# Sensores.net
KiCad netlist of a schematic drawn in Altium Designer
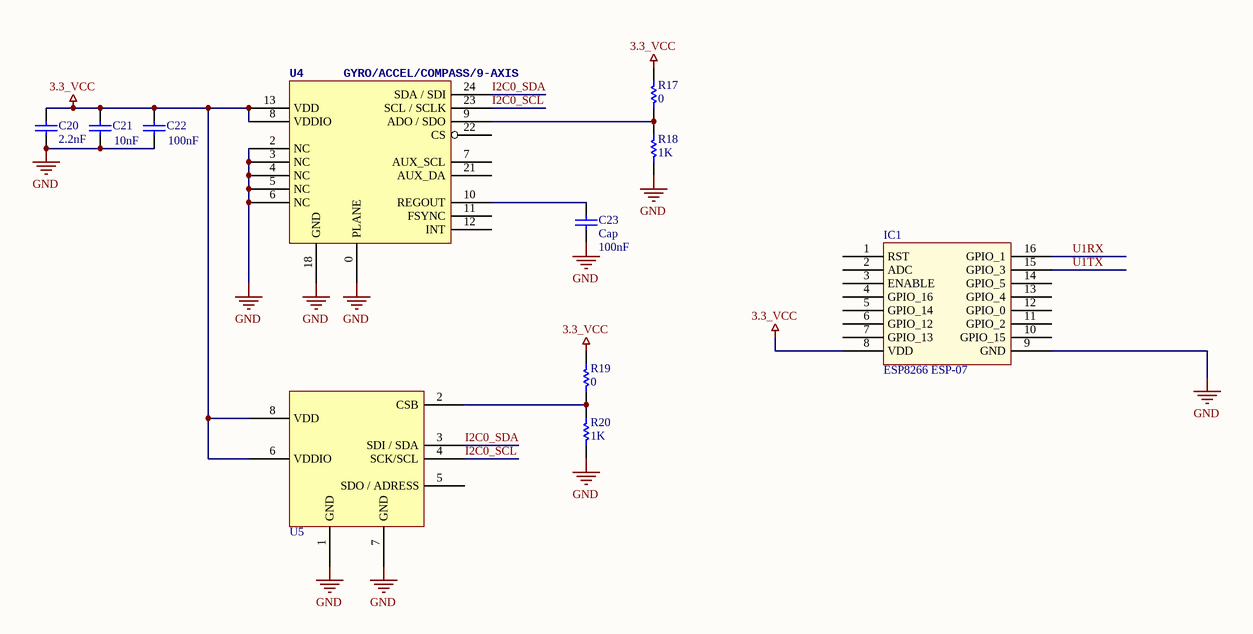
[diagram p0: Sensores.SchDoc]

(export (version "E")
  (design (tool "Eeschema 10.0.6"))
  (components
    (comp (ref "C20")
      (value "2.2nF")
      (footprint "6-0805_L")
      (description "Capacitor")
      (fields (field (name "Comment") "Cap") (field (name "PUBLISHER") "Altium Limited"))
      (libsource (lib "Miscellaneous Devices") (part "Cap"))
    )
    (comp (ref "C21")
      (value "10nF")
      (footprint "6-0805_L")
      (description "Capacitor")
      (fields (field (name "Comment") "Cap") (field (name "PUBLISHER") "Altium Limited"))
      (libsource (lib "Miscellaneous Devices") (part "Cap"))
    )
    (comp (ref "C22")
      (value "100nF")
      (footprint "6-0805_L")
      (description "Capacitor")
      (fields (field (name "Comment") "Cap") (field (name "PUBLISHER") "Altium Limited"))
      (libsource (lib "Miscellaneous Devices") (part "Cap"))
    )
    (comp (ref "C23")
      (value "Cap")
      (footprint "6-0805_L")
      (description "Capacitor")
      (fields (field (name "ALTIUM_VALUE") "100nF") (field (name "PUBLISHER") "Altium Limited"))
      (libsource (lib "Miscellaneous Devices") (part "Cap"))
    )
    (comp (ref "IC1")
      (value "ESP8266 ESP-07")
      (footprint "ESP8266 ESP-ANTENNA")
      (libsource (lib "ESP8266") (part "ESP8266 ESP-07"))
    )
    (comp (ref "R17")
      (value "0")
      (footprint "Miscellaneous Devices:C0805")
      (description "Resistor")
      (fields (field (name "Comment") "Res1") (field (name "PUBLISHER") "Altium Limited"))
      (libsource (lib "Miscellaneous Devices") (part "Res1"))
    )
    (comp (ref "R18")
      (value "1K")
      (footprint "Miscellaneous Devices:C0805")
      (description "Resistor")
      (fields (field (name "Comment") "Res1") (field (name "PUBLISHER") "Altium Limited"))
      (libsource (lib "Miscellaneous Devices") (part "Res1"))
    )
    (comp (ref "R19")
      (value "0")
      (footprint "Miscellaneous Devices:C0805")
      (description "Resistor")
      (fields (field (name "Comment") "Res1") (field (name "PUBLISHER") "Altium Limited"))
      (libsource (lib "Miscellaneous Devices") (part "Res1"))
    )
    (comp (ref "R20")
      (value "1K")
      (footprint "6-0805_L")
      (description "Resistor")
      (fields (field (name "Comment") "Res1") (field (name "PUBLISHER") "Altium Limited"))
      (libsource (lib "Miscellaneous Devices") (part "Res1"))
    )
    (comp (ref "U4")
      (value "GYRO/ACCEL/COMPASS/9-AXIS")
      (footprint "QFN-24/3MM")
      (libsource (lib "MPU-9250") (part "MPU-9250"))
    )
    (comp (ref "U5")
      (value "BMP280")
      (footprint "LGA-8_BMP280(Primary)")
      (description "Barometro")
      (libsource (lib "BMP280") (part "BMP280"))
    )
  )
  (nets
    (net (code "1") (name "/I2C0_SCL") (class "Default")
      (node (ref "U4") (pin "23") (pinfunction "SCL_/_SCLK_23") (pintype "passive"))
      (node (ref "U5") (pin "4") (pinfunction "SCK/SCL_4") (pintype "passive"))
    )
    (net (code "2") (name "/I2C0_SDA") (class "Default")
      (node (ref "U4") (pin "24") (pinfunction "SDA_/_SDI_24") (pintype "passive"))
      (node (ref "U5") (pin "3") (pinfunction "SDI_/_SDA_3") (pintype "passive"))
    )
    (net (code "3") (name "/U1RX") (class "Default")
      (node (ref "IC1") (pin "16") (pinfunction "GPIO_1_16") (pintype "passive"))
    )
    (net (code "4") (name "/U1TX") (class "Default")
      (node (ref "IC1") (pin "15") (pinfunction "GPIO_3_15") (pintype "passive"))
    )
    (net (code "5") (name "3.3_VCC") (class "Default")
      (node (ref "C20") (pin "1") (pinfunction "1_1") (pintype "passive"))
      (node (ref "C21") (pin "2") (pinfunction "2_2") (pintype "passive"))
      (node (ref "C22") (pin "2") (pinfunction "2_2") (pintype "passive"))
      (node (ref "IC1") (pin "8") (pinfunction "VDD_8") (pintype "passive"))
      (node (ref "R17") (pin "2") (pinfunction "2_2") (pintype "passive"))
      (node (ref "R19") (pin "2") (pinfunction "2_2") (pintype "passive"))
      (node (ref "U4") (pin "13") (pinfunction "VDD_13") (pintype "passive"))
      (node (ref "U4") (pin "8") (pinfunction "VDDIO_8") (pintype "passive"))
      (node (ref "U5") (pin "6") (pinfunction "VDDIO_6") (pintype "passive"))
      (node (ref "U5") (pin "8") (pinfunction "VDD_8") (pintype "passive"))
    )
    (net (code "6") (name "GND") (class "Default")
      (node (ref "C20") (pin "2") (pinfunction "2_2") (pintype "passive"))
      (node (ref "C21") (pin "1") (pinfunction "1_1") (pintype "passive"))
      (node (ref "C22") (pin "1") (pinfunction "1_1") (pintype "passive"))
      (node (ref "C23") (pin "1") (pinfunction "1_1") (pintype "passive"))
      (node (ref "IC1") (pin "9") (pinfunction "GND_9") (pintype "passive"))
      (node (ref "R18") (pin "2") (pinfunction "2_2") (pintype "passive"))
      (node (ref "R20") (pin "2") (pinfunction "2_2") (pintype "passive"))
      (node (ref "U4") (pin "0") (pinfunction "PLANE_0") (pintype "passive"))
      (node (ref "U4") (pin "18") (pinfunction "GND_18") (pintype "passive"))
      (node (ref "U4") (pin "2") (pinfunction "NC_2") (pintype "passive"))
      (node (ref "U4") (pin "3") (pinfunction "NC_3") (pintype "passive"))
      (node (ref "U4") (pin "4") (pinfunction "NC_4") (pintype "passive"))
      (node (ref "U4") (pin "5") (pinfunction "NC_5") (pintype "passive"))
      (node (ref "U4") (pin "6") (pinfunction "NC_6") (pintype "passive"))
      (node (ref "U5") (pin "1") (pinfunction "GND_1") (pintype "passive"))
      (node (ref "U5") (pin "7") (pinfunction "GND_7") (pintype "passive"))
    )
    (net (code "7") (name "Net-(U4-ADO_{slash}_SDO)") (class "Default")
      (node (ref "R17") (pin "1") (pinfunction "1_1") (pintype "passive"))
      (node (ref "R18") (pin "1") (pinfunction "1_1") (pintype "passive"))
      (node (ref "U4") (pin "9") (pinfunction "ADO_/_SDO_9") (pintype "passive"))
    )
    (net (code "8") (name "Net-(U4-REGOUT)") (class "Default")
      (node (ref "C23") (pin "2") (pinfunction "2_2") (pintype "passive"))
      (node (ref "U4") (pin "10") (pinfunction "REGOUT_10") (pintype "passive"))
    )
    (net (code "9") (name "Net-(U5-CSB)") (class "Default")
      (node (ref "R19") (pin "1") (pinfunction "1_1") (pintype "passive"))
      (node (ref "R20") (pin "1") (pinfunction "1_1") (pintype "passive"))
      (node (ref "U5") (pin "2") (pinfunction "CSB_2") (pintype "passive"))
    )
    (net (code "10") (name "unconnected-(IC1-ADC-Pad2)") (class "Default")
      (node (ref "IC1") (pin "2") (pinfunction "ADC_2") (pintype "passive"))
    )
    (net (code "11") (name "unconnected-(IC1-ENABLE-Pad3)") (class "Default")
      (node (ref "IC1") (pin "3") (pinfunction "ENABLE_3") (pintype "passive"))
    )
    (net (code "12") (name "unconnected-(IC1-GPIO_0-Pad12)") (class "Default")
      (node (ref "IC1") (pin "12") (pinfunction "GPIO_0_12") (pintype "passive"))
    )
    (net (code "13") (name "unconnected-(IC1-GPIO_2-Pad11)") (class "Default")
      (node (ref "IC1") (pin "11") (pinfunction "GPIO_2_11") (pintype "passive"))
    )
    (net (code "14") (name "unconnected-(IC1-GPIO_4-Pad13)") (class "Default")
      (node (ref "IC1") (pin "13") (pinfunction "GPIO_4_13") (pintype "passive"))
    )
    (net (code "15") (name "unconnected-(IC1-GPIO_5-Pad14)") (class "Default")
      (node (ref "IC1") (pin "14") (pinfunction "GPIO_5_14") (pintype "passive"))
    )
    (net (code "16") (name "unconnected-(IC1-GPIO_12-Pad6)") (class "Default")
      (node (ref "IC1") (pin "6") (pinfunction "GPIO_12_6") (pintype "passive"))
    )
    (net (code "17") (name "unconnected-(IC1-GPIO_13-Pad7)") (class "Default")
      (node (ref "IC1") (pin "7") (pinfunction "GPIO_13_7") (pintype "passive"))
    )
    (net (code "18") (name "unconnected-(IC1-GPIO_14-Pad5)") (class "Default")
      (node (ref "IC1") (pin "5") (pinfunction "GPIO_14_5") (pintype "passive"))
    )
    (net (code "19") (name "unconnected-(IC1-GPIO_15-Pad10)") (class "Default")
      (node (ref "IC1") (pin "10") (pinfunction "GPIO_15_10") (pintype "passive"))
    )
    (net (code "20") (name "unconnected-(IC1-GPIO_16-Pad4)") (class "Default")
      (node (ref "IC1") (pin "4") (pinfunction "GPIO_16_4") (pintype "passive"))
    )
    (net (code "21") (name "unconnected-(IC1-RST-Pad1)") (class "Default")
      (node (ref "IC1") (pin "1") (pinfunction "RST_1") (pintype "passive"))
    )
    (net (code "22") (name "unconnected-(U4-AUX_DA-Pad21)") (class "Default")
      (node (ref "U4") (pin "21") (pinfunction "AUX_DA_21") (pintype "passive"))
    )
    (net (code "23") (name "unconnected-(U4-AUX_SCL-Pad7)") (class "Default")
      (node (ref "U4") (pin "7") (pinfunction "AUX_SCL_7") (pintype "passive"))
    )
    (net (code "24") (name "unconnected-(U4-CS-Pad22)") (class "Default")
      (node (ref "U4") (pin "22") (pinfunction "CS_22") (pintype "passive"))
    )
    (net (code "25") (name "unconnected-(U4-FSYNC-Pad11)") (class "Default")
      (node (ref "U4") (pin "11") (pinfunction "FSYNC_11") (pintype "passive"))
    )
    (net (code "26") (name "unconnected-(U4-INT-Pad12)") (class "Default")
      (node (ref "U4") (pin "12") (pinfunction "INT_12") (pintype "passive"))
    )
    (net (code "27") (name "unconnected-(U5-SDO_{slash}_ADRESS-Pad5)") (class "Default")
      (node (ref "U5") (pin "5") (pinfunction "SDO_/_ADRESS_5") (pintype "passive"))
    )
  )
)
